# addressHold.net
KiCad netlist of a schematic drawn in EAGLE
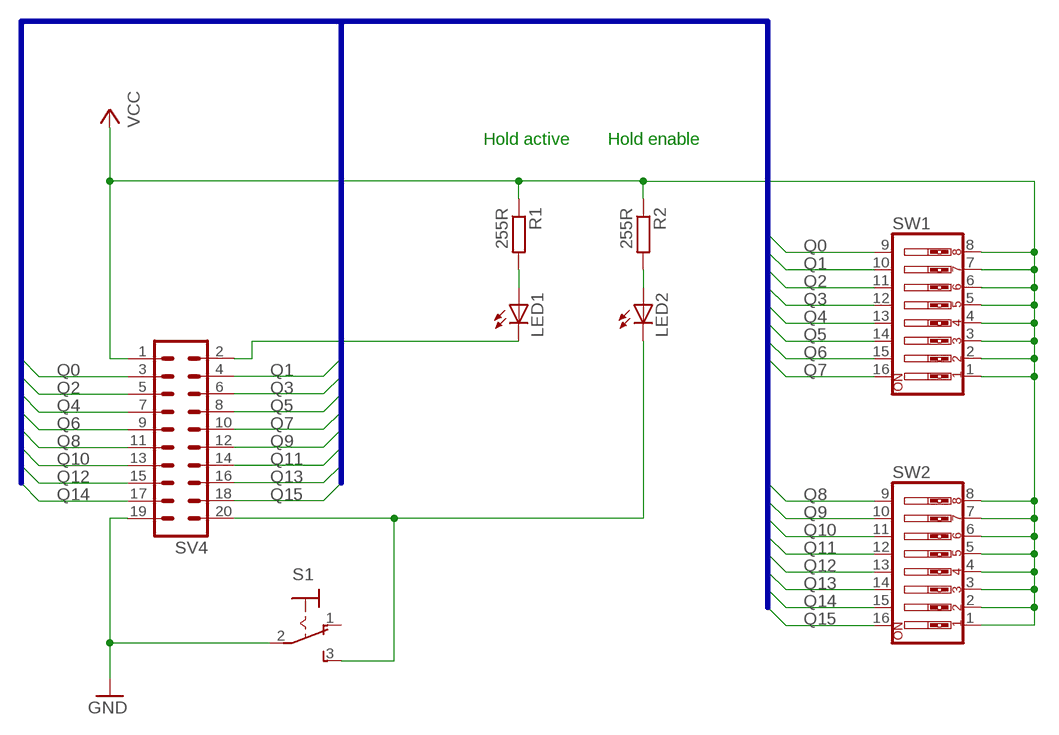
[diagram p0: schematic, sheet 1]

(export (version "E")
  (design (tool "Eeschema 10.0.6"))
  (components
    (comp (ref "LED1")
      (value "LED5MM")
      (footprint "eagle-import:LED5MM")
      (libsource (lib "eagle-import") (part "LED5MM"))
    )
    (comp (ref "LED2")
      (value "LED5MM")
      (footprint "eagle-import:LED5MM")
      (libsource (lib "eagle-import") (part "LED5MM"))
    )
    (comp (ref "R1")
      (value "255R")
      (footprint "eagle-import:0204_5")
      (libsource (lib "eagle-import") (part "R-EU_0204/5"))
    )
    (comp (ref "R2")
      (value "255R")
      (footprint "eagle-import:0204_5")
      (libsource (lib "eagle-import") (part "R-EU_0204/5"))
    )
    (comp (ref "S1")
      (value "320-916")
      (footprint "eagle-import:320-916")
      (libsource (lib "eagle-import") (part "320-916"))
    )
    (comp (ref "SV4")
      (value "ML20L")
      (footprint "eagle-import:ML20L")
      (libsource (lib "eagle-import") (part "ML20L"))
    )
    (comp (ref "SW1")
      (value "SW_DIP-8")
      (footprint "eagle-import:EDG-08")
      (libsource (lib "eagle-import") (part "SW_DIP-8"))
    )
    (comp (ref "SW2")
      (value "SW_DIP-8")
      (footprint "eagle-import:EDG-08")
      (libsource (lib "eagle-import") (part "SW_DIP-8"))
    )
  )
  (nets
    (net (code "1") (name "/Q0") (class "Default")
      (node (ref "SV4") (pin "3") (pinfunction "3_3") (pintype "passive"))
      (node (ref "SW1") (pin "9") (pinfunction "9_9") (pintype "passive"))
    )
    (net (code "2") (name "/Q1") (class "Default")
      (node (ref "SV4") (pin "4") (pinfunction "4_4") (pintype "passive"))
      (node (ref "SW1") (pin "10") (pinfunction "10_10") (pintype "passive"))
    )
    (net (code "3") (name "/Q2") (class "Default")
      (node (ref "SV4") (pin "5") (pinfunction "5_5") (pintype "passive"))
      (node (ref "SW1") (pin "11") (pinfunction "11_11") (pintype "passive"))
    )
    (net (code "4") (name "/Q3") (class "Default")
      (node (ref "SV4") (pin "6") (pinfunction "6_6") (pintype "passive"))
      (node (ref "SW1") (pin "12") (pinfunction "12_12") (pintype "passive"))
    )
    (net (code "5") (name "/Q4") (class "Default")
      (node (ref "SV4") (pin "7") (pinfunction "7_7") (pintype "passive"))
      (node (ref "SW1") (pin "13") (pinfunction "13_13") (pintype "passive"))
    )
    (net (code "6") (name "/Q5") (class "Default")
      (node (ref "SV4") (pin "8") (pinfunction "8_8") (pintype "passive"))
      (node (ref "SW1") (pin "14") (pinfunction "14_14") (pintype "passive"))
    )
    (net (code "7") (name "/Q6") (class "Default")
      (node (ref "SV4") (pin "9") (pinfunction "9_9") (pintype "passive"))
      (node (ref "SW1") (pin "15") (pinfunction "15_15") (pintype "passive"))
    )
    (net (code "8") (name "/Q7") (class "Default")
      (node (ref "SV4") (pin "10") (pinfunction "10_10") (pintype "passive"))
      (node (ref "SW1") (pin "16") (pinfunction "16_16") (pintype "passive"))
    )
    (net (code "9") (name "/Q8") (class "Default")
      (node (ref "SV4") (pin "11") (pinfunction "11_11") (pintype "passive"))
      (node (ref "SW2") (pin "9") (pinfunction "9_9") (pintype "passive"))
    )
    (net (code "10") (name "/Q9") (class "Default")
      (node (ref "SV4") (pin "12") (pinfunction "12_12") (pintype "passive"))
      (node (ref "SW2") (pin "10") (pinfunction "10_10") (pintype "passive"))
    )
    (net (code "11") (name "/Q10") (class "Default")
      (node (ref "SV4") (pin "13") (pinfunction "13_13") (pintype "passive"))
      (node (ref "SW2") (pin "11") (pinfunction "11_11") (pintype "passive"))
    )
    (net (code "12") (name "/Q11") (class "Default")
      (node (ref "SV4") (pin "14") (pinfunction "14_14") (pintype "passive"))
      (node (ref "SW2") (pin "12") (pinfunction "12_12") (pintype "passive"))
    )
    (net (code "13") (name "/Q12") (class "Default")
      (node (ref "SV4") (pin "15") (pinfunction "15_15") (pintype "passive"))
      (node (ref "SW2") (pin "13") (pinfunction "13_13") (pintype "passive"))
    )
    (net (code "14") (name "/Q13") (class "Default")
      (node (ref "SV4") (pin "16") (pinfunction "16_16") (pintype "passive"))
      (node (ref "SW2") (pin "14") (pinfunction "14_14") (pintype "passive"))
    )
    (net (code "15") (name "/Q14") (class "Default")
      (node (ref "SV4") (pin "17") (pinfunction "17_17") (pintype "passive"))
      (node (ref "SW2") (pin "15") (pinfunction "15_15") (pintype "passive"))
    )
    (net (code "16") (name "/Q15") (class "Default")
      (node (ref "SV4") (pin "18") (pinfunction "18_18") (pintype "passive"))
      (node (ref "SW2") (pin "16") (pinfunction "16_16") (pintype "passive"))
    )
    (net (code "17") (name "GND") (class "Default")
      (node (ref "S1") (pin "2") (pinfunction "P_2") (pintype "passive"))
      (node (ref "SV4") (pin "19") (pinfunction "19_19") (pintype "passive"))
    )
    (net (code "18") (name "Net-(LED1-C)") (class "Default")
      (node (ref "LED1") (pin "K") (pinfunction "C_K") (pintype "passive"))
      (node (ref "SV4") (pin "2") (pinfunction "2_2") (pintype "passive"))
    )
    (net (code "19") (name "Net-(LED1-PadA)") (class "Default")
      (node (ref "LED1") (pin "A") (pinfunction "A_A") (pintype "passive"))
      (node (ref "R1") (pin "2") (pinfunction "2_2") (pintype "passive"))
    )
    (net (code "20") (name "Net-(LED2-C)") (class "Default")
      (node (ref "LED2") (pin "K") (pinfunction "C_K") (pintype "passive"))
      (node (ref "S1") (pin "3") (pinfunction "S_3") (pintype "passive"))
      (node (ref "SV4") (pin "20") (pinfunction "20_20") (pintype "passive"))
    )
    (net (code "21") (name "Net-(LED2-PadA)") (class "Default")
      (node (ref "LED2") (pin "A") (pinfunction "A_A") (pintype "passive"))
      (node (ref "R2") (pin "2") (pinfunction "2_2") (pintype "passive"))
    )
    (net (code "22") (name "VCC") (class "Default")
      (node (ref "R1") (pin "1") (pinfunction "1_1") (pintype "passive"))
      (node (ref "R2") (pin "1") (pinfunction "1_1") (pintype "passive"))
      (node (ref "SV4") (pin "1") (pinfunction "1_1") (pintype "passive"))
      (node (ref "SW1") (pin "1") (pinfunction "1_1") (pintype "passive"))
      (node (ref "SW1") (pin "2") (pinfunction "2_2") (pintype "passive"))
      (node (ref "SW1") (pin "3") (pinfunction "3_3") (pintype "passive"))
      (node (ref "SW1") (pin "4") (pinfunction "4_4") (pintype "passive"))
      (node (ref "SW1") (pin "5") (pinfunction "5_5") (pintype "passive"))
      (node (ref "SW1") (pin "6") (pinfunction "6_6") (pintype "passive"))
      (node (ref "SW1") (pin "7") (pinfunction "7_7") (pintype "passive"))
      (node (ref "SW1") (pin "8") (pinfunction "8_8") (pintype "passive"))
      (node (ref "SW2") (pin "1") (pinfunction "1_1") (pintype "passive"))
      (node (ref "SW2") (pin "2") (pinfunction "2_2") (pintype "passive"))
      (node (ref "SW2") (pin "3") (pinfunction "3_3") (pintype "passive"))
      (node (ref "SW2") (pin "4") (pinfunction "4_4") (pintype "passive"))
      (node (ref "SW2") (pin "5") (pinfunction "5_5") (pintype "passive"))
      (node (ref "SW2") (pin "6") (pinfunction "6_6") (pintype "passive"))
      (node (ref "SW2") (pin "7") (pinfunction "7_7") (pintype "passive"))
      (node (ref "SW2") (pin "8") (pinfunction "8_8") (pintype "passive"))
    )
    (net (code "23") (name "unconnected-(S1-O-Pad1)") (class "Default")
      (node (ref "S1") (pin "1") (pinfunction "O_1") (pintype "passive"))
    )
  )
)
